# HDD.net
KiCad netlist of a schematic drawn in Altium Designer
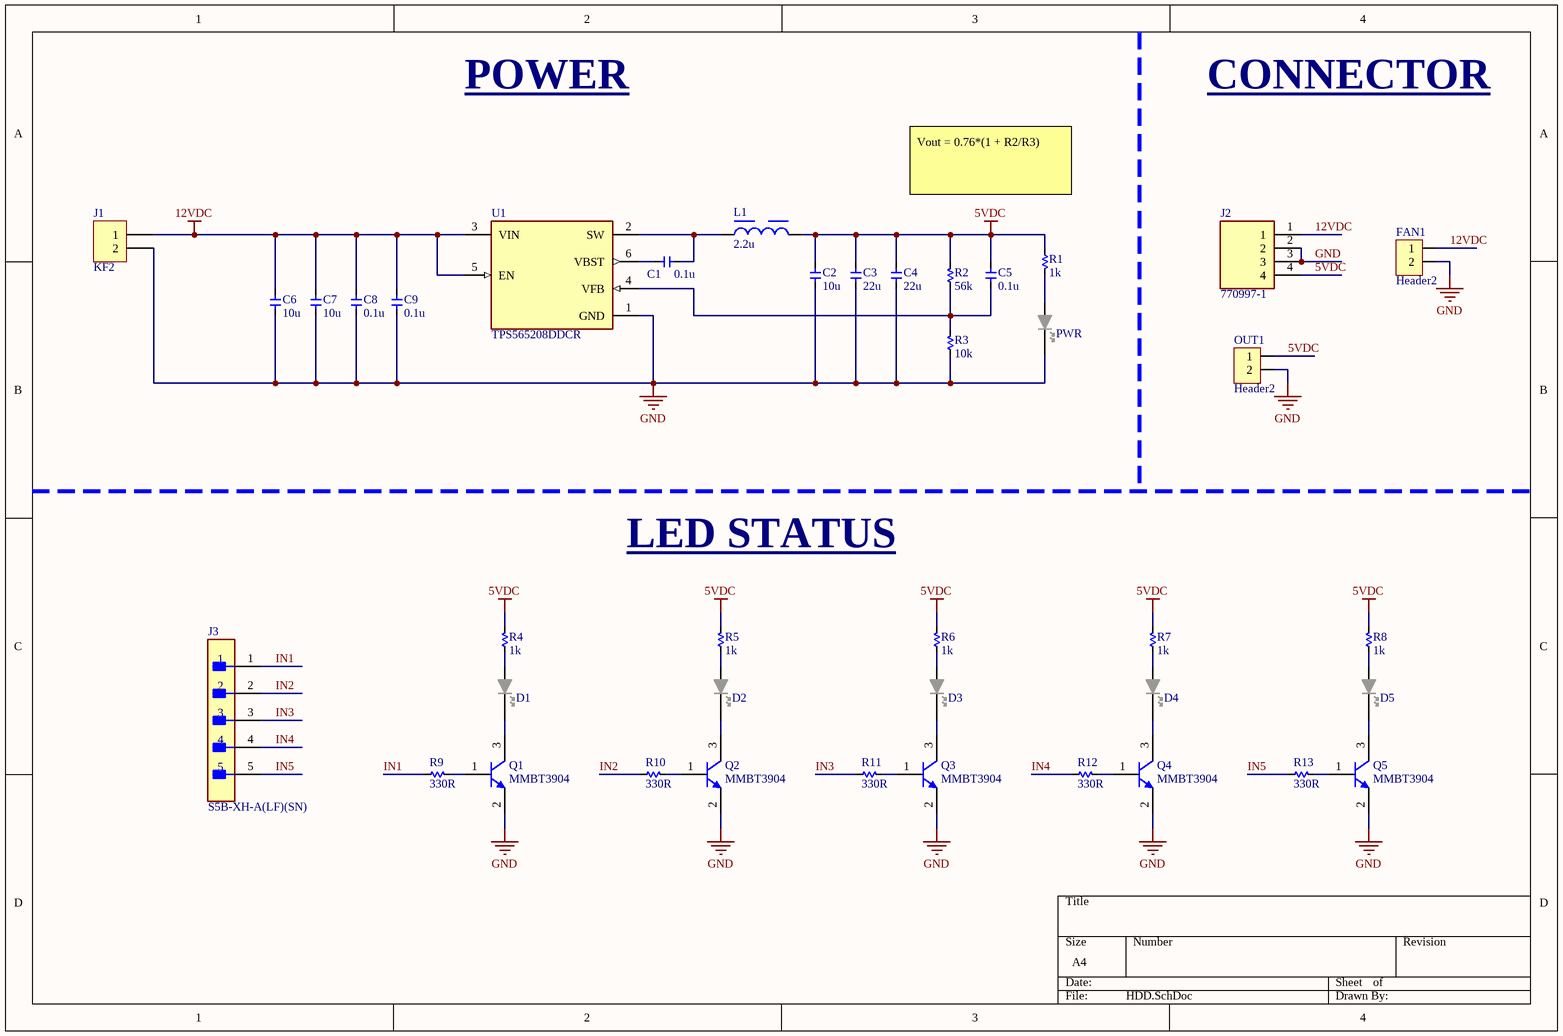
[diagram p0: HDD.SchDoc]

(export (version "E")
  (design (tool "Eeschema 10.0.6"))
  (components
    (comp (ref "C1")
      (value "0.1u")
      (footprint "CAP-CER-0603")
      (libsource (lib "Electronic Components") (part "Non-Polar Cap"))
    )
    (comp (ref "C2")
      (value "10u")
      (footprint "CAP-CER-0603")
      (libsource (lib "Electronic Components") (part "Non-Polar Cap"))
    )
    (comp (ref "C3")
      (value "22u")
      (footprint "CAP-CER-0603")
      (libsource (lib "Electronic Components") (part "Non-Polar Cap"))
    )
    (comp (ref "C4")
      (value "22u")
      (footprint "CAP-CER-0603")
      (libsource (lib "Electronic Components") (part "Non-Polar Cap"))
    )
    (comp (ref "C5")
      (value "0.1u")
      (footprint "CAP-CER-0603")
      (libsource (lib "Electronic Components") (part "Non-Polar Cap"))
    )
    (comp (ref "C6")
      (value "10u")
      (footprint "CAP-CER-0603")
      (libsource (lib "Electronic Components") (part "Non-Polar Cap"))
    )
    (comp (ref "C7")
      (value "10u")
      (footprint "CAP-CER-0603")
      (libsource (lib "Electronic Components") (part "Non-Polar Cap"))
    )
    (comp (ref "C8")
      (value "0.1u")
      (footprint "CAP-CER-0603")
      (libsource (lib "Electronic Components") (part "Non-Polar Cap"))
    )
    (comp (ref "C9")
      (value "0.1u")
      (footprint "CAP-CER-0603")
      (libsource (lib "Electronic Components") (part "Non-Polar Cap"))
    )
    (comp (ref "D1")
      (value "LED")
      (footprint "SLM-490")
      (description "5mm LED Holder Height 16.1mm (w/o LED)")
      (fields (field (name "MANUFACTURER") "BIVAR") (field (name "MANUFACTURER PART NUMBER") "SLM-490"))
      (libsource (lib "PhilsLab Lib") (part "LED_5MM_HOLDER_16MM1"))
    )
    (comp (ref "D2")
      (value "LED")
      (footprint "SLM-490")
      (description "5mm LED Holder Height 16.1mm (w/o LED)")
      (fields (field (name "MANUFACTURER") "BIVAR") (field (name "MANUFACTURER PART NUMBER") "SLM-490"))
      (libsource (lib "PhilsLab Lib") (part "LED_5MM_HOLDER_16MM1"))
    )
    (comp (ref "D3")
      (value "LED")
      (footprint "SLM-490")
      (description "5mm LED Holder Height 16.1mm (w/o LED)")
      (fields (field (name "MANUFACTURER") "BIVAR") (field (name "MANUFACTURER PART NUMBER") "SLM-490"))
      (libsource (lib "PhilsLab Lib") (part "LED_5MM_HOLDER_16MM1"))
    )
    (comp (ref "D4")
      (value "LED")
      (footprint "SLM-490")
      (description "5mm LED Holder Height 16.1mm (w/o LED)")
      (fields (field (name "MANUFACTURER") "BIVAR") (field (name "MANUFACTURER PART NUMBER") "SLM-490"))
      (libsource (lib "PhilsLab Lib") (part "LED_5MM_HOLDER_16MM1"))
    )
    (comp (ref "D5")
      (value "LED")
      (footprint "SLM-490")
      (description "5mm LED Holder Height 16.1mm (w/o LED)")
      (fields (field (name "MANUFACTURER") "BIVAR") (field (name "MANUFACTURER PART NUMBER") "SLM-490"))
      (libsource (lib "PhilsLab Lib") (part "LED_5MM_HOLDER_16MM1"))
    )
    (comp (ref "FAN1")
      (value "Header2")
      (footprint "Header2")
      (description "Header IDC, 2 x 1 Pin Vertical 2.54mm Pitch (Non-Boxed, Male)")
      (fields
        (field (name "MANUFACTURER") "Würth Elektronik eiSos GmbH")
        (field (name "PARTNO") "613002143121")
        (field (name "CREATED BY") "Karrer Zheng")
      )
      (libsource (lib "TechMT.VN_Lib_Project v2") (part "Header2"))
    )
    (comp (ref "J1")
      (value "KF2")
      (footprint "KF2-7.62")
      (fields
        (field (name "MANUFACTURER") "Würth Elektronik eiSos GmbH")
        (field (name "PARTNO") "691103110002")
        (field (name "CREATED BY") "Karrer Zheng")
      )
      (libsource (lib "TechMT.VN_Lib_Project v2") (part "KF2"))
    )
    (comp (ref "J2")
      (value "770997-1")
      (footprint "SamacSys:RHDR4W158P0X508_1X4_2540X965X1156P")
      (description "Connector")
      (fields (field (name "MOUSER PART NUMBER") "571-7709971"))
      (libsource (lib "*") (part "770997-1"))
    )
    (comp (ref "J3")
      (value "S5B-XH-A(LF)(SN)")
      (footprint "FP-S5B-XH-A_LF_SN-MFG")
      (description "CONN HEADER R/A 5POS 2.5MM")
      (libsource (lib "Altium Content Vault") (part "bf93c07fd2649a848d0ec8585582aab"))
    )
    (comp (ref "L1")
      (value "2.2u")
      (footprint "WE-HCI_7040")
      (fields (field (name "TOLERANCE") "20%"))
      (libsource (lib "Altium Content Vault") (part "Inductor - 3"))
    )
    (comp (ref "OUT1")
      (value "Header2")
      (footprint "Header2")
      (description "Header IDC, 2 x 1 Pin Vertical 2.54mm Pitch (Non-Boxed, Male)")
      (fields
        (field (name "MANUFACTURER") "Würth Elektronik eiSos GmbH")
        (field (name "PARTNO") "613002143121")
        (field (name "CREATED BY") "Karrer Zheng")
      )
      (libsource (lib "TechMT.VN_Lib_Project v2") (part "Header2"))
    )
    (comp (ref "PWR")
      (value "LED")
      (footprint "SLM-490")
      (description "5mm LED Holder Height 16.1mm (w/o LED)")
      (fields (field (name "MANUFACTURER") "BIVAR") (field (name "MANUFACTURER PART NUMBER") "SLM-490"))
      (libsource (lib "PhilsLab Lib") (part "LED_5MM_HOLDER_16MM1"))
    )
    (comp (ref "Q1")
      (value "MMBT3904")
      (footprint "FAIR-SOT23-3_V")
      (description "NPN General Purpose Amplifier, 40 V, 0.2 A, -55 to 150 degC, 3-Pin SOT23, RoHS, Tape and Reel")
      (fields (field (name "TOLERANCE") "30ppm"))
      (libsource (lib "Altium Content Vault") (part "BJT-NPN-BEC-3"))
    )
    (comp (ref "Q2")
      (value "MMBT3904")
      (footprint "FAIR-SOT23-3_V")
      (description "NPN General Purpose Amplifier, 40 V, 0.2 A, -55 to 150 degC, 3-Pin SOT23, RoHS, Tape and Reel")
      (fields (field (name "TOLERANCE") "30ppm"))
      (libsource (lib "Altium Content Vault") (part "BJT-NPN-BEC-3"))
    )
    (comp (ref "Q3")
      (value "MMBT3904")
      (footprint "FAIR-SOT23-3_V")
      (description "NPN General Purpose Amplifier, 40 V, 0.2 A, -55 to 150 degC, 3-Pin SOT23, RoHS, Tape and Reel")
      (fields (field (name "TOLERANCE") "30ppm"))
      (libsource (lib "Altium Content Vault") (part "BJT-NPN-BEC-3"))
    )
    (comp (ref "Q4")
      (value "MMBT3904")
      (footprint "FAIR-SOT23-3_V")
      (description "NPN General Purpose Amplifier, 40 V, 0.2 A, -55 to 150 degC, 3-Pin SOT23, RoHS, Tape and Reel")
      (fields (field (name "TOLERANCE") "30ppm"))
      (libsource (lib "Altium Content Vault") (part "BJT-NPN-BEC-3"))
    )
    (comp (ref "Q5")
      (value "MMBT3904")
      (footprint "FAIR-SOT23-3_V")
      (description "NPN General Purpose Amplifier, 40 V, 0.2 A, -55 to 150 degC, 3-Pin SOT23, RoHS, Tape and Reel")
      (fields (field (name "TOLERANCE") "30ppm"))
      (libsource (lib "Altium Content Vault") (part "BJT-NPN-BEC-3"))
    )
    (comp (ref "R1")
      (value "1k")
      (footprint "RES-SMD-0603")
      (libsource (lib "Electronic Components") (part "Res"))
    )
    (comp (ref "R2")
      (value "56k")
      (footprint "RES-SMD-0603")
      (libsource (lib "Electronic Components") (part "Res"))
    )
    (comp (ref "R3")
      (value "10k")
      (footprint "RES-SMD-0603")
      (libsource (lib "Electronic Components") (part "Res"))
    )
    (comp (ref "R4")
      (value "1k")
      (footprint "RES-SMD-0603")
      (libsource (lib "Electronic Components") (part "Res"))
    )
    (comp (ref "R5")
      (value "1k")
      (footprint "RES-SMD-0603")
      (libsource (lib "Electronic Components") (part "Res"))
    )
    (comp (ref "R6")
      (value "1k")
      (footprint "RES-SMD-0603")
      (libsource (lib "Electronic Components") (part "Res"))
    )
    (comp (ref "R7")
      (value "1k")
      (footprint "RES-SMD-0603")
      (libsource (lib "Electronic Components") (part "Res"))
    )
    (comp (ref "R8")
      (value "1k")
      (footprint "RES-SMD-0603")
      (libsource (lib "Electronic Components") (part "Res"))
    )
    (comp (ref "R9")
      (value "330R")
      (footprint "RES-SMD-0603")
      (libsource (lib "Electronic Components") (part "Res"))
    )
    (comp (ref "R10")
      (value "330R")
      (footprint "RES-SMD-0603")
      (libsource (lib "Electronic Components") (part "Res"))
    )
    (comp (ref "R11")
      (value "330R")
      (footprint "RES-SMD-0603")
      (libsource (lib "Electronic Components") (part "Res"))
    )
    (comp (ref "R12")
      (value "330R")
      (footprint "RES-SMD-0603")
      (libsource (lib "Electronic Components") (part "Res"))
    )
    (comp (ref "R13")
      (value "330R")
      (footprint "RES-SMD-0603")
      (libsource (lib "Electronic Components") (part "Res"))
    )
    (comp (ref "U1")
      (value "TPS565208DDCR")
      (footprint "FP-DDC0006A-IPC_A")
      (description "IC REG BUCK ADJ 5A TSOT23-6")
      (libsource (lib "Altium Content Vault") (part "031fd0dc84c0aa7f0f34afede0be814"))
    )
  )
  (nets
    (net (code "1") (name "/IN1") (class "Default")
      (node (ref "J3") (pin "1") (pinfunction "1_1") (pintype "passive"))
      (node (ref "R9") (pin "1") (pinfunction "1_1") (pintype "passive"))
    )
    (net (code "2") (name "/IN2") (class "Default")
      (node (ref "J3") (pin "2") (pinfunction "2_2") (pintype "passive"))
      (node (ref "R10") (pin "1") (pinfunction "1_1") (pintype "passive"))
    )
    (net (code "3") (name "/IN3") (class "Default")
      (node (ref "J3") (pin "3") (pinfunction "3_3") (pintype "passive"))
      (node (ref "R11") (pin "1") (pinfunction "1_1") (pintype "passive"))
    )
    (net (code "4") (name "/IN4") (class "Default")
      (node (ref "J3") (pin "4") (pinfunction "4_4") (pintype "passive"))
      (node (ref "R12") (pin "1") (pinfunction "1_1") (pintype "passive"))
    )
    (net (code "5") (name "/IN5") (class "Default")
      (node (ref "J3") (pin "5") (pinfunction "5_5") (pintype "passive"))
      (node (ref "R13") (pin "1") (pinfunction "1_1") (pintype "passive"))
    )
    (net (code "6") (name "5VDC") (class "Default")
      (node (ref "C2") (pin "2") (pinfunction "2_2") (pintype "passive"))
      (node (ref "C3") (pin "2") (pinfunction "2_2") (pintype "passive"))
      (node (ref "C4") (pin "2") (pinfunction "2_2") (pintype "passive"))
      (node (ref "C5") (pin "2") (pinfunction "2_2") (pintype "passive"))
      (node (ref "J2") (pin "4") (pinfunction "4_4") (pintype "passive"))
      (node (ref "L1") (pin "2") (pinfunction "2_2") (pintype "passive"))
      (node (ref "OUT1") (pin "1") (pinfunction "1_1") (pintype "passive"))
      (node (ref "R1") (pin "1") (pinfunction "1_1") (pintype "passive"))
      (node (ref "R2") (pin "2") (pinfunction "2_2") (pintype "passive"))
      (node (ref "R4") (pin "2") (pinfunction "2_2") (pintype "passive"))
      (node (ref "R5") (pin "2") (pinfunction "2_2") (pintype "passive"))
      (node (ref "R6") (pin "2") (pinfunction "2_2") (pintype "passive"))
      (node (ref "R7") (pin "2") (pinfunction "2_2") (pintype "passive"))
      (node (ref "R8") (pin "2") (pinfunction "2_2") (pintype "passive"))
    )
    (net (code "7") (name "12VDC") (class "Default")
      (node (ref "C6") (pin "2") (pinfunction "2_2") (pintype "passive"))
      (node (ref "C7") (pin "2") (pinfunction "2_2") (pintype "passive"))
      (node (ref "C8") (pin "2") (pinfunction "2_2") (pintype "passive"))
      (node (ref "C9") (pin "2") (pinfunction "2_2") (pintype "passive"))
      (node (ref "FAN1") (pin "1") (pinfunction "1_1") (pintype "passive"))
      (node (ref "J1") (pin "1") (pinfunction "1_1") (pintype "passive"))
      (node (ref "J2") (pin "1") (pinfunction "1_1") (pintype "passive"))
      (node (ref "U1") (pin "3") (pinfunction "VIN_3") (pintype "power_in"))
      (node (ref "U1") (pin "5") (pinfunction "EN_5") (pintype "input"))
    )
    (net (code "8") (name "GND") (class "Default")
      (node (ref "C2") (pin "1") (pinfunction "1_1") (pintype "passive"))
      (node (ref "C3") (pin "1") (pinfunction "1_1") (pintype "passive"))
      (node (ref "C4") (pin "1") (pinfunction "1_1") (pintype "passive"))
      (node (ref "C6") (pin "1") (pinfunction "1_1") (pintype "passive"))
      (node (ref "C7") (pin "1") (pinfunction "1_1") (pintype "passive"))
      (node (ref "C8") (pin "1") (pinfunction "1_1") (pintype "passive"))
      (node (ref "C9") (pin "1") (pinfunction "1_1") (pintype "passive"))
      (node (ref "FAN1") (pin "2") (pinfunction "2_2") (pintype "passive"))
      (node (ref "J1") (pin "2") (pinfunction "2_2") (pintype "passive"))
      (node (ref "J2") (pin "2") (pinfunction "2_2") (pintype "passive"))
      (node (ref "J2") (pin "3") (pinfunction "3_3") (pintype "passive"))
      (node (ref "OUT1") (pin "2") (pinfunction "2_2") (pintype "passive"))
      (node (ref "PWR") (pin "K") (pinfunction "K_K") (pintype "passive"))
      (node (ref "Q1") (pin "2") (pinfunction "E_2") (pintype "passive"))
      (node (ref "Q2") (pin "2") (pinfunction "E_2") (pintype "passive"))
      (node (ref "Q3") (pin "2") (pinfunction "E_2") (pintype "passive"))
      (node (ref "Q4") (pin "2") (pinfunction "E_2") (pintype "passive"))
      (node (ref "Q5") (pin "2") (pinfunction "E_2") (pintype "passive"))
      (node (ref "R3") (pin "1") (pinfunction "1_1") (pintype "passive"))
      (node (ref "U1") (pin "1") (pinfunction "GND_1") (pintype "power_in"))
    )
    (net (code "9") (name "Net-(D1-PadA)") (class "Default")
      (node (ref "D1") (pin "A") (pinfunction "A_A") (pintype "passive"))
      (node (ref "R4") (pin "1") (pinfunction "1_1") (pintype "passive"))
    )
    (net (code "10") (name "Net-(D2-PadA)") (class "Default")
      (node (ref "D2") (pin "A") (pinfunction "A_A") (pintype "passive"))
      (node (ref "R5") (pin "1") (pinfunction "1_1") (pintype "passive"))
    )
    (net (code "11") (name "Net-(D3-PadA)") (class "Default")
      (node (ref "D3") (pin "A") (pinfunction "A_A") (pintype "passive"))
      (node (ref "R6") (pin "1") (pinfunction "1_1") (pintype "passive"))
    )
    (net (code "12") (name "Net-(D4-PadA)") (class "Default")
      (node (ref "D4") (pin "A") (pinfunction "A_A") (pintype "passive"))
      (node (ref "R7") (pin "1") (pinfunction "1_1") (pintype "passive"))
    )
    (net (code "13") (name "Net-(D5-PadA)") (class "Default")
      (node (ref "D5") (pin "A") (pinfunction "A_A") (pintype "passive"))
      (node (ref "R8") (pin "1") (pinfunction "1_1") (pintype "passive"))
    )
    (net (code "14") (name "Net-(PWR-PadA)") (class "Default")
      (node (ref "PWR") (pin "A") (pinfunction "A_A") (pintype "passive"))
      (node (ref "R1") (pin "2") (pinfunction "2_2") (pintype "passive"))
    )
    (net (code "15") (name "Net-(Q1-B)") (class "Default")
      (node (ref "Q1") (pin "1") (pinfunction "B_1") (pintype "passive"))
      (node (ref "R9") (pin "2") (pinfunction "2_2") (pintype "passive"))
    )
    (net (code "16") (name "Net-(Q1-C)") (class "Default")
      (node (ref "D1") (pin "K") (pinfunction "K_K") (pintype "passive"))
      (node (ref "Q1") (pin "3") (pinfunction "C_3") (pintype "passive"))
    )
    (net (code "17") (name "Net-(Q2-B)") (class "Default")
      (node (ref "Q2") (pin "1") (pinfunction "B_1") (pintype "passive"))
      (node (ref "R10") (pin "2") (pinfunction "2_2") (pintype "passive"))
    )
    (net (code "18") (name "Net-(Q2-C)") (class "Default")
      (node (ref "D2") (pin "K") (pinfunction "K_K") (pintype "passive"))
      (node (ref "Q2") (pin "3") (pinfunction "C_3") (pintype "passive"))
    )
    (net (code "19") (name "Net-(Q3-B)") (class "Default")
      (node (ref "Q3") (pin "1") (pinfunction "B_1") (pintype "passive"))
      (node (ref "R11") (pin "2") (pinfunction "2_2") (pintype "passive"))
    )
    (net (code "20") (name "Net-(Q3-C)") (class "Default")
      (node (ref "D3") (pin "K") (pinfunction "K_K") (pintype "passive"))
      (node (ref "Q3") (pin "3") (pinfunction "C_3") (pintype "passive"))
    )
    (net (code "21") (name "Net-(Q4-B)") (class "Default")
      (node (ref "Q4") (pin "1") (pinfunction "B_1") (pintype "passive"))
      (node (ref "R12") (pin "2") (pinfunction "2_2") (pintype "passive"))
    )
    (net (code "22") (name "Net-(Q4-C)") (class "Default")
      (node (ref "D4") (pin "K") (pinfunction "K_K") (pintype "passive"))
      (node (ref "Q4") (pin "3") (pinfunction "C_3") (pintype "passive"))
    )
    (net (code "23") (name "Net-(Q5-B)") (class "Default")
      (node (ref "Q5") (pin "1") (pinfunction "B_1") (pintype "passive"))
      (node (ref "R13") (pin "2") (pinfunction "2_2") (pintype "passive"))
    )
    (net (code "24") (name "Net-(Q5-C)") (class "Default")
      (node (ref "D5") (pin "K") (pinfunction "K_K") (pintype "passive"))
      (node (ref "Q5") (pin "3") (pinfunction "C_3") (pintype "passive"))
    )
    (net (code "25") (name "Net-(U1-SW)") (class "Default")
      (node (ref "C1") (pin "1") (pinfunction "1_1") (pintype "passive"))
      (node (ref "L1") (pin "1") (pinfunction "1_1") (pintype "passive"))
      (node (ref "U1") (pin "2") (pinfunction "SW_2") (pintype "power_in"))
    )
    (net (code "26") (name "Net-(U1-VBST)") (class "Default")
      (node (ref "C1") (pin "2") (pinfunction "2_2") (pintype "passive"))
      (node (ref "U1") (pin "6") (pinfunction "VBST_6") (pintype "output"))
    )
    (net (code "27") (name "Net-(U1-VFB)") (class "Default")
      (node (ref "C5") (pin "1") (pinfunction "1_1") (pintype "passive"))
      (node (ref "R2") (pin "1") (pinfunction "1_1") (pintype "passive"))
      (node (ref "R3") (pin "2") (pinfunction "2_2") (pintype "passive"))
      (node (ref "U1") (pin "4") (pinfunction "VFB_4") (pintype "input"))
    )
  )
)
